# bq3DP_LCD.net
KiCad netlist of a schematic drawn in Altium Designer
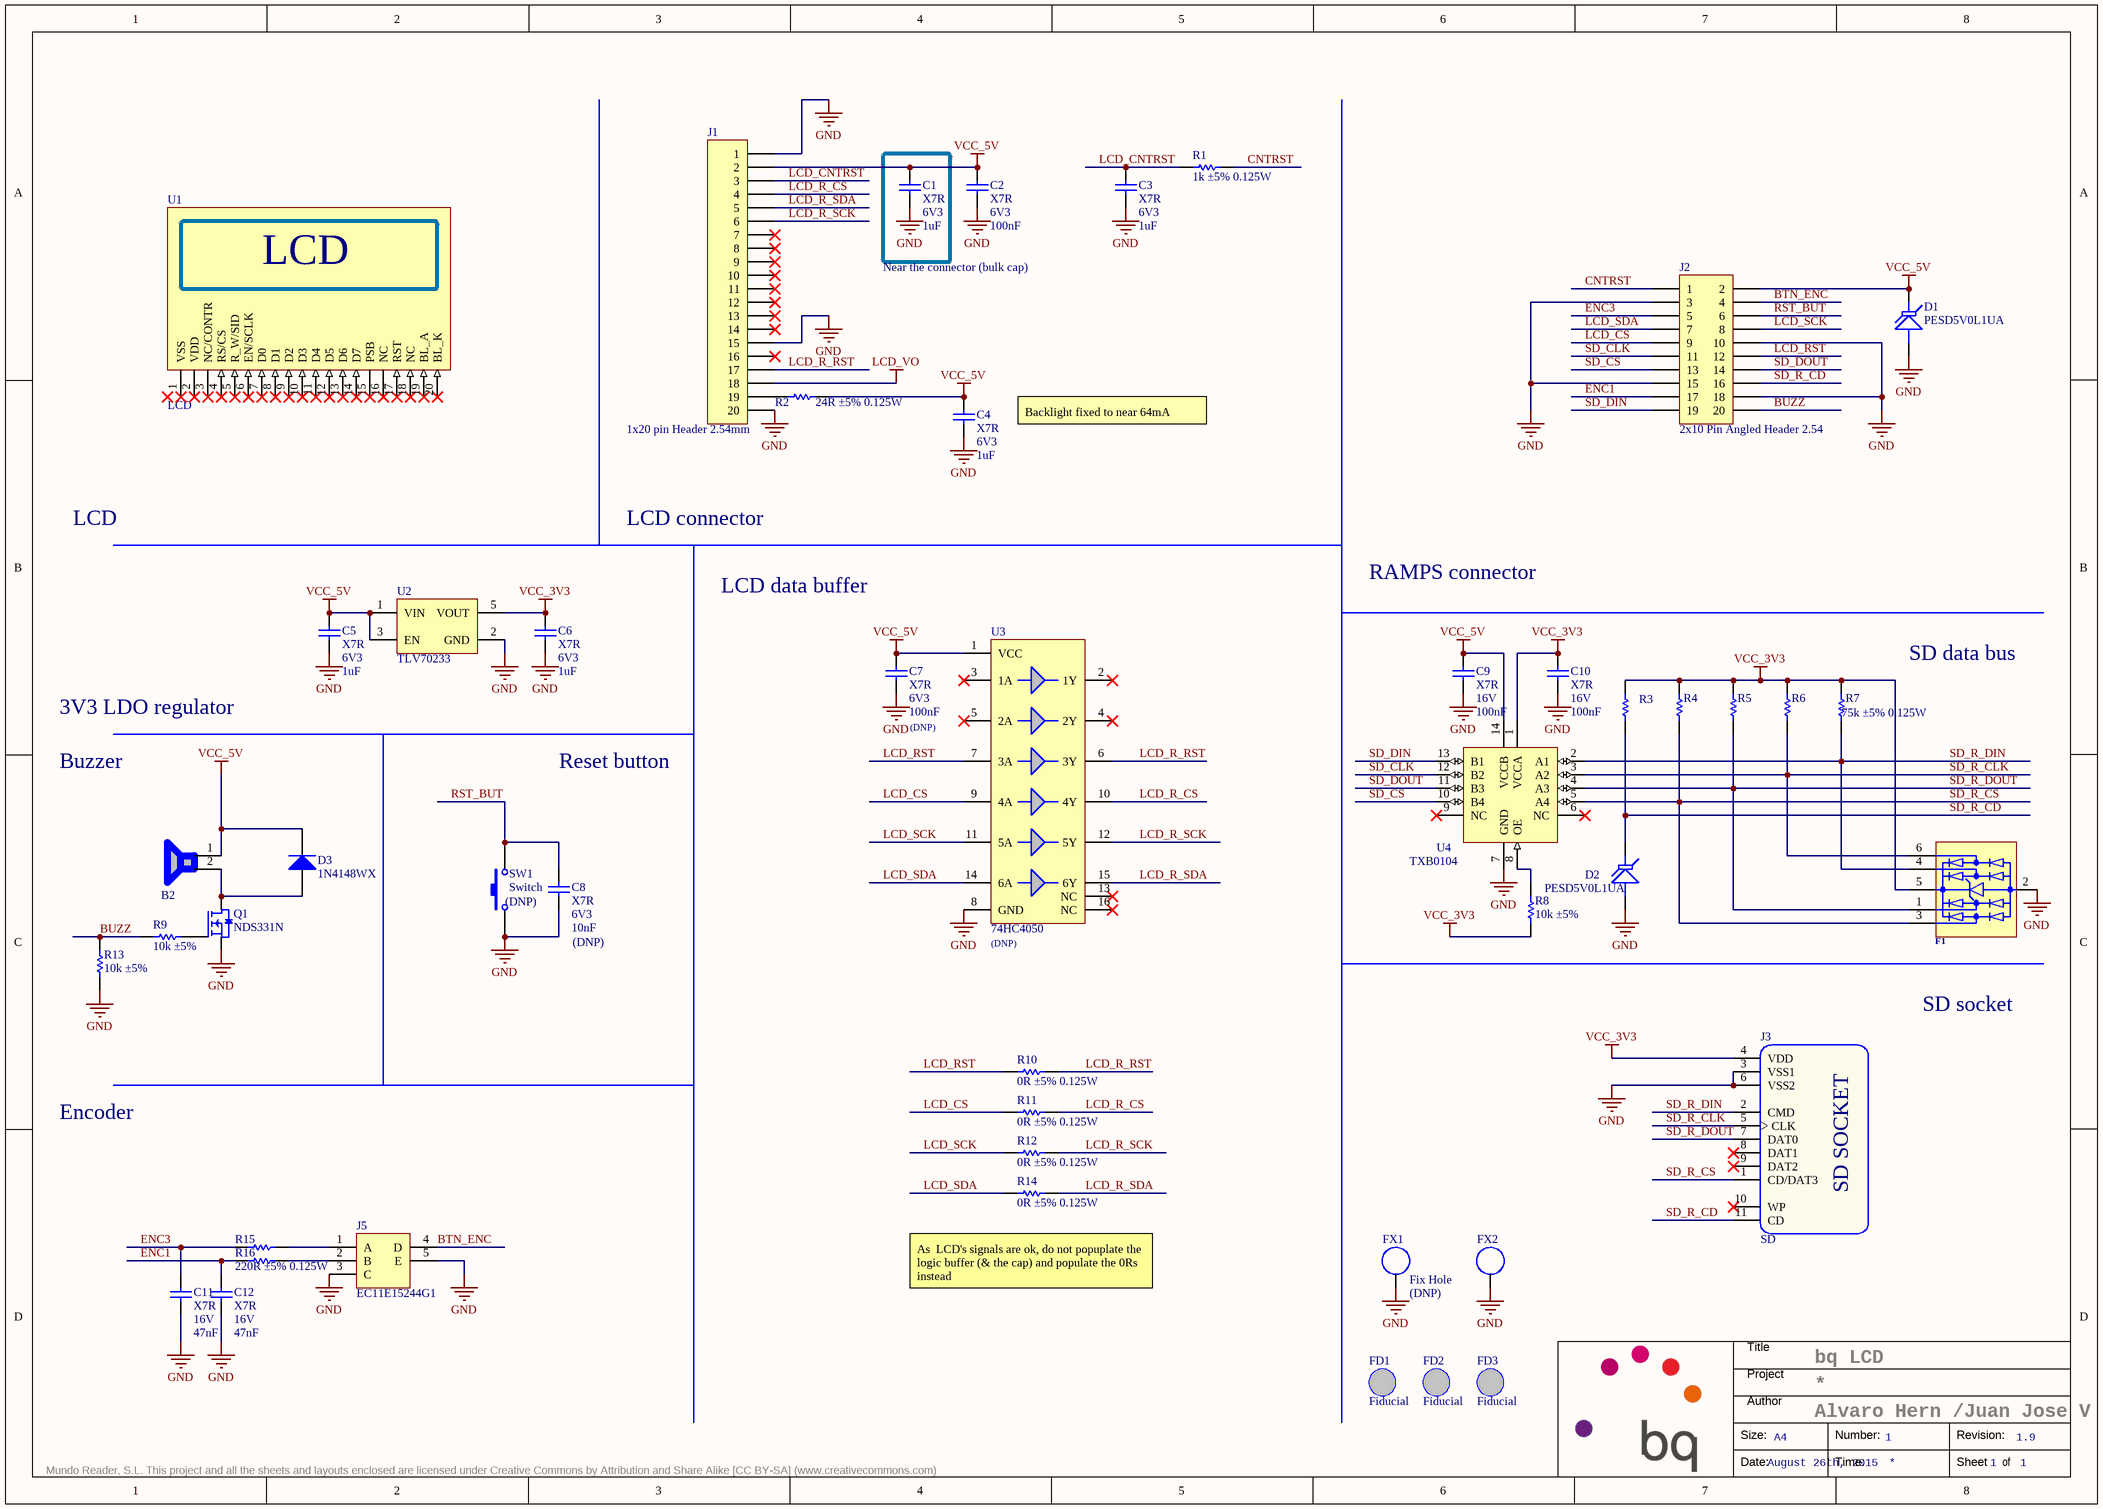
[diagram p0: bq3DP_LCD.SchDoc]

(export (version "E")
  (design (tool "Eeschema 10.0.6"))
  (components
    (comp (ref "B2")
      (value "BUZZER")
      (footprint "KXG1205C")
      (description "Buzzer")
      (fields (field (name "MANUFACTURER") "Kingstate Elect.") (field (name "PART NUMBER") "KXG1205C"))
      (libsource (lib "Electromechanical") (part "BUZZER"))
    )
    (comp (ref "C1")
      (value "Capacitor")
      (footprint "C0805")
      (fields
        (field (name "DIELECTRIC") "X7R")
        (field (name "VOLTAGE") "6V3")
        (field (name "CAPACITANCE") "1uF")
        (field (name "PART NUMBER") "C0805_1uF_6V3_±10%")
        (field (name "TOLERANCE") "±10%")
        (field (name "MANUFACTURER") "Kemet")
      )
      (libsource (lib "Pasives_Capacitor_SMD") (part "Capacitor"))
    )
    (comp (ref "C2")
      (value "Capacitor")
      (footprint "C0805")
      (fields
        (field (name "DIELECTRIC") "X7R")
        (field (name "VOLTAGE") "6V3")
        (field (name "CAPACITANCE") "100nF")
        (field (name "PART NUMBER") "C0805_100nF_6V3_±10%")
        (field (name "TOLERANCE") "±10%")
        (field (name "MANUFACTURER") "Kemet")
      )
      (libsource (lib "Pasives_Capacitor_SMD") (part "Capacitor"))
    )
    (comp (ref "C3")
      (value "Capacitor")
      (footprint "C0805")
      (fields
        (field (name "DIELECTRIC") "X7R")
        (field (name "VOLTAGE") "6V3")
        (field (name "CAPACITANCE") "1uF")
        (field (name "PART NUMBER") "C0805_1uF_6V3_±10%")
        (field (name "TOLERANCE") "±10%")
        (field (name "MANUFACTURER") "Kemet")
      )
      (libsource (lib "Pasives_Capacitor_SMD") (part "Capacitor"))
    )
    (comp (ref "C4")
      (value "Capacitor")
      (footprint "C0805")
      (fields
        (field (name "DIELECTRIC") "X7R")
        (field (name "VOLTAGE") "6V3")
        (field (name "CAPACITANCE") "1uF")
        (field (name "PART NUMBER") "C0805_1uF_6V3_±10%")
        (field (name "TOLERANCE") "±10%")
        (field (name "MANUFACTURER") "Kemet")
      )
      (libsource (lib "Pasives_Capacitor_SMD") (part "Capacitor"))
    )
    (comp (ref "C5")
      (value "Capacitor")
      (footprint "C0805")
      (fields
        (field (name "DIELECTRIC") "X7R")
        (field (name "VOLTAGE") "6V3")
        (field (name "CAPACITANCE") "1uF")
        (field (name "PART NUMBER") "C0805_1uF_6V3_±10%")
        (field (name "TOLERANCE") "±10%")
        (field (name "MANUFACTURER") "Kemet")
      )
      (libsource (lib "Pasives_Capacitor_SMD") (part "Capacitor"))
    )
    (comp (ref "C6")
      (value "Capacitor")
      (footprint "C0805")
      (fields
        (field (name "DIELECTRIC") "X7R")
        (field (name "VOLTAGE") "6V3")
        (field (name "CAPACITANCE") "1uF")
        (field (name "PART NUMBER") "C0805_1uF_6V3_±10%")
        (field (name "TOLERANCE") "±10%")
        (field (name "MANUFACTURER") "Kemet")
      )
      (libsource (lib "Pasives_Capacitor_SMD") (part "Capacitor"))
    )
    (comp (ref "C7")
      (value "Capacitor")
      (footprint "C0805")
      (fields
        (field (name "DIELECTRIC") "X7R")
        (field (name "VOLTAGE") "6V3")
        (field (name "CAPACITANCE") "100nF")
        (field (name "PART NUMBER") "C0805_100nF_6V3_±10%")
        (field (name "TOLERANCE") "±10%")
        (field (name "MANUFACTURER") "Kemet")
        (field (name "VARIANT") "(DNP)")
      )
      (libsource (lib "Pasives_Capacitor_SMD") (part "Capacitor"))
    )
    (comp (ref "C8")
      (value "Capacitor")
      (footprint "C0805")
      (fields
        (field (name "DIELECTRIC") "X7R")
        (field (name "VOLTAGE") "6V3")
        (field (name "CAPACITANCE") "10nF")
        (field (name "PART NUMBER") "C0805_10nF_6V3_±10%")
        (field (name "TOLERANCE") "±10%")
        (field (name "MANUFACTURER") "Kemet")
        (field (name "VARIANT") "(DNP)")
      )
      (libsource (lib "Pasives_Capacitor_SMD") (part "Capacitor"))
    )
    (comp (ref "C9")
      (value "Capacitor")
      (footprint "C0805")
      (description "Capacitor SMD")
      (fields
        (field (name "DIELECTRIC") "X7R")
        (field (name "VOLTAGE") "16V")
        (field (name "CAPACITANCE") "100nF")
        (field (name "PART NUMBER") "C0805_100nF_16V_±10%")
        (field (name "TOLERANCE") "±10%")
      )
      (libsource (lib "Pasives_Capacitor_SMD") (part "Capacitor"))
    )
    (comp (ref "C10")
      (value "Capacitor")
      (footprint "C0805")
      (description "Capacitor SMD")
      (fields
        (field (name "DIELECTRIC") "X7R")
        (field (name "VOLTAGE") "16V")
        (field (name "CAPACITANCE") "100nF")
        (field (name "PART NUMBER") "C0805_100nF_16V_±10%")
        (field (name "TOLERANCE") "±10%")
      )
      (libsource (lib "Pasives_Capacitor_SMD") (part "Capacitor"))
    )
    (comp (ref "C11")
      (value "Capacitor")
      (footprint "C0805")
      (description "Capacitor SMD")
      (fields
        (field (name "DIELECTRIC") "X7R")
        (field (name "VOLTAGE") "16V")
        (field (name "CAPACITANCE") "47nF")
        (field (name "PART NUMBER") "C0805_47nF_16V_±10%")
        (field (name "TOLERANCE") "±10%")
      )
      (libsource (lib "Pasives_Capacitor_SMD") (part "Capacitor"))
    )
    (comp (ref "C12")
      (value "Capacitor")
      (footprint "C0805")
      (description "Capacitor SMD")
      (fields
        (field (name "DIELECTRIC") "X7R")
        (field (name "VOLTAGE") "16V")
        (field (name "CAPACITANCE") "47nF")
        (field (name "PART NUMBER") "C0805_47nF_16V_±10%")
        (field (name "TOLERANCE") "±10%")
      )
      (libsource (lib "Pasives_Capacitor_SMD") (part "Capacitor"))
    )
    (comp (ref "D1")
      (value "PESD5V0L1UA")
      (footprint "SOD323")
      (description "Transient Suppression Diodes")
      (fields (field (name "VOLTAGE") "5Vdc") (field (name "MANUFACTURER") "NXP"))
      (libsource (lib "Protection") (part "Zener_TVS"))
    )
    (comp (ref "D2")
      (value "PESD5V0L1UA")
      (footprint "SOD323")
      (description "Transient Suppression Diodes")
      (fields (field (name "VOLTAGE") "5Vdc") (field (name "MANUFACTURER") "NXP"))
      (libsource (lib "Protection") (part "Zener_TVS"))
    )
    (comp (ref "D3")
      (value "1N4148WX")
      (footprint "SOD323")
      (description "Diodo")
      (fields (field (name "MANUFACTURER") "Micro Commercial Components"))
      (libsource (lib "Semiconductors_Diodes") (part "Diodo"))
    )
    (comp (ref "F1")
      (value "IP4220CZ6")
      (footprint "SOT23-6")
      (description "USB Dual ESD Protection")
      (fields (field (name "PART NUMBER") "USB ESD") (field (name "MANUFACTURER") "NXP"))
      (libsource (lib "Protection") (part "IP4220CZ6"))
    )
    (comp (ref "FD1")
      (value "Fiducial")
      (footprint "Fiducial")
      (libsource (lib "Miscelanea") (part "Fiducial"))
    )
    (comp (ref "FD2")
      (value "Fiducial")
      (footprint "Fiducial")
      (libsource (lib "Miscelanea") (part "Fiducial"))
    )
    (comp (ref "FD3")
      (value "Fiducial")
      (footprint "Fiducial")
      (libsource (lib "Miscelanea") (part "Fiducial"))
    )
    (comp (ref "FX1")
      (value "Fix Hole")
      (footprint "74760045")
      (fields
        (field (name "PART NUMBER") "Earth connection")
        (field (name "MANUFACTURER") "Wurth")
        (field (name "VARIANT") "(DNP)")
      )
      (libsource (lib "Miscelanea") (part "Fix Hole"))
    )
    (comp (ref "FX2")
      (value "Fix Hole")
      (footprint "7466214")
      (fields (field (name "PART NUMBER") "Earth SMD connection") (field (name "MANUFACTURER") "Wurth"))
      (libsource (lib "Miscelanea") (part "Fix Hole"))
    )
    (comp (ref "J1")
      (value "1x20 pin Header 2.54mm")
      (footprint "1x20 Pin Header 2.54")
      (fields (field (name "PART NUMBER") "CON_PH_THT2.54_20") (field (name "MANUFACTURER") "Samtec"))
      (libsource (lib "Conectores_PinHeader_2.54") (part "1x20 pin Header 2.54mm"))
    )
    (comp (ref "J2")
      (value "2x10 Pin Angled Header 2.54")
      (footprint "2x10 Pin Angled Header 2.54")
      (description "20 pin Dual Angled Header 2.54mm")
      (fields (field (name "PART NUMBER") "CON_DPH_THTA2.54_20") (field (name "MANUFACTURER") "Samtec"))
      (libsource (lib "Conectores_PinHeader_2.54") (part "2x10 Pin Angled Header 2.54"))
    )
    (comp (ref "J3")
      (value "SD")
      (footprint "SD")
      (fields (field (name "MANUFACTURER") "Wurth"))
      (libsource (lib "Connectors_Storage") (part "SD"))
    )
    (comp (ref "J5")
      (value "Encoder_ALPS")
      (footprint "Encoder_EC11")
      (description "Encoder 2-ph w/button ALPS")
      (fields
        (field (name "ORDERINGCODE") "EC11E15244G1")
        (field (name "MANUFACTURER") "ALPS")
        (field (name "PART NUMBER") "Encoder_EC11")
      )
      (libsource (lib "Electromechanical") (part "Encoder_ALPS"))
    )
    (comp (ref "Q1")
      (value "NDS331N")
      (footprint "SOT23-3")
      (description "Mosfet Channel N Enhancement Mode")
      (fields (field (name "MANUFACTURER") "Fairchild Semiconductor"))
      (libsource (lib "Semiconductors_Transistors") (part "Mosfet_N"))
    )
    (comp (ref "R1")
      (value "1k ±5% 0.125W")
      (footprint "R0805")
      (description "Resistor")
      (fields (field (name "TOLERANCE") "±5%") (field (name "POWER") "0.125W"))
      (libsource (lib "Pasives_Resistor_SMD") (part "Resistor"))
    )
    (comp (ref "R2")
      (value "24R ±5% 0.125W")
      (footprint "R0805")
      (description "Resistor")
      (fields (field (name "TOLERANCE") "±5%") (field (name "POWER") "0.125W"))
      (libsource (lib "Pasives_Resistor_SMD") (part "Resistor"))
    )
    (comp (ref "R3")
      (value "Resistor")
      (footprint "R0805")
      (description "Resistor, SMD")
      (fields (field (name "TOLERANCE") "±5%") (field (name "POWER") "0.125W"))
      (libsource (lib "Pasives_Resistor_SMD") (part "Resistor"))
    )
    (comp (ref "R4")
      (value "Resistor")
      (footprint "R0805")
      (description "Resistor, SMD")
      (fields (field (name "TOLERANCE") "±5%") (field (name "POWER") "0.125W"))
      (libsource (lib "Pasives_Resistor_SMD") (part "Resistor"))
    )
    (comp (ref "R5")
      (value "Resistor")
      (footprint "R0805")
      (description "Resistor, SMD")
      (fields (field (name "TOLERANCE") "±5%") (field (name "POWER") "0.125W"))
      (libsource (lib "Pasives_Resistor_SMD") (part "Resistor"))
    )
    (comp (ref "R6")
      (value "Resistor")
      (footprint "R0805")
      (description "Resistor, SMD")
      (fields (field (name "TOLERANCE") "±5%") (field (name "POWER") "0.125W"))
      (libsource (lib "Pasives_Resistor_SMD") (part "Resistor"))
    )
    (comp (ref "R7")
      (value "75k ±5% 0.125W")
      (footprint "R0805")
      (description "Resistor, SMD")
      (fields (field (name "TOLERANCE") "±5%") (field (name "POWER") "0.125W"))
      (libsource (lib "Pasives_Resistor_SMD") (part "Resistor"))
    )
    (comp (ref "R8")
      (value "10k ±5%")
      (footprint "R0805")
      (description "Resistor")
      (fields (field (name "TOLERANCE") "±5%") (field (name "POWER") "0.125W"))
      (libsource (lib "Pasives_Resistor_SMD") (part "Resistor"))
    )
    (comp (ref "R9")
      (value "10k ±5%")
      (footprint "R0805")
      (description "Resistor")
      (fields (field (name "TOLERANCE") "±5%") (field (name "POWER") "0.125W"))
      (libsource (lib "Pasives_Resistor_SMD") (part "Resistor"))
    )
    (comp (ref "R10")
      (value "0R ±5% 0.125W")
      (footprint "R0805")
      (description "Resistor, SMD")
      (fields (field (name "TOLERANCE") "±5%") (field (name "POWER") "0.125W"))
      (libsource (lib "Pasives_Resistor_SMD") (part "Resistor"))
    )
    (comp (ref "R11")
      (value "0R ±5% 0.125W")
      (footprint "R0805")
      (description "Resistor, SMD")
      (fields (field (name "TOLERANCE") "±5%") (field (name "POWER") "0.125W"))
      (libsource (lib "Pasives_Resistor_SMD") (part "Resistor"))
    )
    (comp (ref "R12")
      (value "0R ±5% 0.125W")
      (footprint "R0805")
      (description "Resistor, SMD")
      (fields (field (name "TOLERANCE") "±5%") (field (name "POWER") "0.125W"))
      (libsource (lib "Pasives_Resistor_SMD") (part "Resistor"))
    )
    (comp (ref "R13")
      (value "10k ±5%")
      (footprint "R0805")
      (description "Resistor")
      (fields (field (name "TOLERANCE") "±5%") (field (name "POWER") "0.125W"))
      (libsource (lib "Pasives_Resistor_SMD") (part "Resistor"))
    )
    (comp (ref "R14")
      (value "0R ±5% 0.125W")
      (footprint "R0805")
      (description "Resistor, SMD")
      (fields (field (name "TOLERANCE") "±5%") (field (name "POWER") "0.125W"))
      (libsource (lib "Pasives_Resistor_SMD") (part "Resistor"))
    )
    (comp (ref "R15")
      (value "Resistor")
      (footprint "R0805")
      (description "Resistor, SMD")
      (fields (field (name "TOLERANCE") "±5%") (field (name "POWER") "0.125W"))
      (libsource (lib "Pasives_Resistor_SMD") (part "Resistor"))
    )
    (comp (ref "R16")
      (value "220R ±5% 0.125W")
      (footprint "R0805")
      (description "Resistor, SMD")
      (fields (field (name "TOLERANCE") "±5%") (field (name "POWER") "0.125W"))
      (libsource (lib "Pasives_Resistor_SMD") (part "Resistor"))
    )
    (comp (ref "SW1")
      (value "Switch")
      (footprint "SW_SMD_6.0x3.8")
      (description "Micro miniature pushbutton surface Switch")
      (fields
        (field (name "PART NUMBER") "SW SMD")
        (field (name "MANUFACTURER") "Würth Elektronik")
        (field (name "VARIANT") "(DNP)")
      )
      (libsource (lib "Electromechanical") (part "Switch"))
    )
    (comp (ref "U1")
      (value "LCD")
      (footprint "LCD_Graphic_128x64")
      (description "LCD 128x64 dot 93x70mm")
      (fields (field (name "PART NUMBER") "LCD_graph") (field (name "MANUFACTURER") "Winstar"))
      (libsource (lib "Optoelectronics") (part "LCD"))
    )
    (comp (ref "U2")
      (value "TLV70233")
      (footprint "SOT23-5")
      (description "300mA LowIQ Low-dropout Regulator")
      (fields (field (name "MANUFACTURER") "Texas Instruments"))
      (libsource (lib "Power_Regulator") (part "TLV702XX"))
    )
    (comp (ref "U3")
      (value "74HC4050")
      (footprint "SO16")
      (description "Hex non-inverting HIGH-to-LOW level shifter")
      (fields
        (field (name "PART NUMBER") "HEF4050B")
        (field (name "MANUFACTURER") "NXP")
        (field (name "VARIANT") "(DNP)")
      )
      (libsource (lib "Transceiver") (part "74HC4050"))
    )
    (comp (ref "U4")
      (value "TXB0104")
      (footprint "QFN14")
      (description "Voltage Translator, Quad")
      (fields (field (name "MANUFACTURER") "Texas Instruments"))
      (libsource (lib "Voltage_translator") (part "TXB0104"))
    )
  )
  (nets
    (net (code "1") (name "/BTN_ENC") (class "Default")
      (node (ref "J2") (pin "4") (pinfunction "4_4") (pintype "passive"))
      (node (ref "J5") (pin "4") (pinfunction "D_4") (pintype "power_in"))
    )
    (net (code "2") (name "/BUZZ") (class "Default")
      (node (ref "J2") (pin "20") (pinfunction "20_20") (pintype "passive"))
      (node (ref "R13") (pin "2") (pinfunction "2_2") (pintype "passive"))
      (node (ref "R9") (pin "2") (pinfunction "2_2") (pintype "passive"))
    )
    (net (code "3") (name "/CNTRST") (class "Default")
      (node (ref "J2") (pin "1") (pinfunction "1_1") (pintype "passive"))
      (node (ref "R1") (pin "2") (pinfunction "2_2") (pintype "passive"))
    )
    (net (code "4") (name "/ENC1") (class "Default")
      (node (ref "C12") (pin "2") (pinfunction "2_2") (pintype "passive"))
      (node (ref "J2") (pin "17") (pinfunction "17_17") (pintype "passive"))
      (node (ref "R16") (pin "1") (pinfunction "1_1") (pintype "passive"))
    )
    (net (code "5") (name "/ENC3") (class "Default")
      (node (ref "C11") (pin "2") (pinfunction "2_2") (pintype "passive"))
      (node (ref "J2") (pin "5") (pinfunction "5_5") (pintype "passive"))
      (node (ref "R15") (pin "1") (pinfunction "1_1") (pintype "passive"))
    )
    (net (code "6") (name "/LCD_CNTRST") (class "Default")
      (node (ref "C3") (pin "2") (pinfunction "2_2") (pintype "passive"))
      (node (ref "J1") (pin "3") (pinfunction "3_3") (pintype "passive"))
      (node (ref "R1") (pin "1") (pinfunction "1_1") (pintype "passive"))
    )
    (net (code "7") (name "/LCD_CS") (class "Default")
      (node (ref "J2") (pin "9") (pinfunction "9_9") (pintype "passive"))
      (node (ref "R11") (pin "1") (pinfunction "1_1") (pintype "passive"))
      (node (ref "U3") (pin "9") (pinfunction "4A_9") (pintype "power_in"))
    )
    (net (code "8") (name "/LCD_RST") (class "Default")
      (node (ref "J2") (pin "12") (pinfunction "12_12") (pintype "passive"))
      (node (ref "R10") (pin "1") (pinfunction "1_1") (pintype "passive"))
      (node (ref "U3") (pin "7") (pinfunction "3A_7") (pintype "power_in"))
    )
    (net (code "9") (name "/LCD_R_CS") (class "Default")
      (node (ref "J1") (pin "4") (pinfunction "4_4") (pintype "passive"))
      (node (ref "R11") (pin "2") (pinfunction "2_2") (pintype "passive"))
      (node (ref "U3") (pin "10") (pinfunction "4Y_10") (pintype "power_in"))
    )
    (net (code "10") (name "/LCD_R_RST") (class "Default")
      (node (ref "J1") (pin "17") (pinfunction "17_17") (pintype "passive"))
      (node (ref "R10") (pin "2") (pinfunction "2_2") (pintype "passive"))
      (node (ref "U3") (pin "6") (pinfunction "3Y_6") (pintype "power_in"))
    )
    (net (code "11") (name "/LCD_R_SCK") (class "Default")
      (node (ref "J1") (pin "6") (pinfunction "6_6") (pintype "passive"))
      (node (ref "R12") (pin "2") (pinfunction "2_2") (pintype "passive"))
      (node (ref "U3") (pin "12") (pinfunction "5Y_12") (pintype "power_in"))
    )
    (net (code "12") (name "/LCD_R_SDA") (class "Default")
      (node (ref "J1") (pin "5") (pinfunction "5_5") (pintype "passive"))
      (node (ref "R14") (pin "2") (pinfunction "2_2") (pintype "passive"))
      (node (ref "U3") (pin "15") (pinfunction "6Y_15") (pintype "power_in"))
    )
    (net (code "13") (name "/LCD_SCK") (class "Default")
      (node (ref "J2") (pin "8") (pinfunction "8_8") (pintype "passive"))
      (node (ref "R12") (pin "1") (pinfunction "1_1") (pintype "passive"))
      (node (ref "U3") (pin "11") (pinfunction "5A_11") (pintype "power_in"))
    )
    (net (code "14") (name "/LCD_SDA") (class "Default")
      (node (ref "J2") (pin "7") (pinfunction "7_7") (pintype "passive"))
      (node (ref "R14") (pin "1") (pinfunction "1_1") (pintype "passive"))
      (node (ref "U3") (pin "14") (pinfunction "6A_14") (pintype "power_in"))
    )
    (net (code "15") (name "/RST_BUT") (class "Default")
      (node (ref "C8") (pin "2") (pinfunction "2_2") (pintype "passive"))
      (node (ref "J2") (pin "6") (pinfunction "6_6") (pintype "passive"))
      (node (ref "SW1") (pin "2") (pinfunction "2_2") (pintype "passive"))
    )
    (net (code "16") (name "/SD_CLK") (class "Default")
      (node (ref "J2") (pin "11") (pinfunction "11_11") (pintype "passive"))
      (node (ref "U4") (pin "12") (pinfunction "B2_12") (pintype "bidirectional"))
    )
    (net (code "17") (name "/SD_CS") (class "Default")
      (node (ref "J2") (pin "13") (pinfunction "13_13") (pintype "passive"))
      (node (ref "U4") (pin "10") (pinfunction "B4_10") (pintype "bidirectional"))
    )
    (net (code "18") (name "/SD_DIN") (class "Default")
      (node (ref "J2") (pin "19") (pinfunction "19_19") (pintype "passive"))
      (node (ref "U4") (pin "13") (pinfunction "B1_13") (pintype "bidirectional"))
    )
    (net (code "19") (name "/SD_DOUT") (class "Default")
      (node (ref "J2") (pin "14") (pinfunction "14_14") (pintype "passive"))
      (node (ref "U4") (pin "11") (pinfunction "B3_11") (pintype "bidirectional"))
    )
    (net (code "20") (name "/SD_R_CD") (class "Default")
      (node (ref "D2") (pin "K") (pinfunction "K_K") (pintype "passive"))
      (node (ref "J2") (pin "16") (pinfunction "16_16") (pintype "passive"))
      (node (ref "J3") (pin "11") (pinfunction "CD_11") (pintype "passive"))
      (node (ref "R3") (pin "1") (pinfunction "1_1") (pintype "passive"))
    )
    (net (code "21") (name "/SD_R_CLK") (class "Default")
      (node (ref "F1") (pin "6") (pinfunction "6_6") (pintype "passive"))
      (node (ref "J3") (pin "5") (pinfunction "CLK_5") (pintype "passive"))
      (node (ref "R6") (pin "1") (pinfunction "1_1") (pintype "passive"))
      (node (ref "U4") (pin "3") (pinfunction "A2_3") (pintype "bidirectional"))
    )
    (net (code "22") (name "/SD_R_CS") (class "Default")
      (node (ref "F1") (pin "3") (pinfunction "3_3") (pintype "passive"))
      (node (ref "J3") (pin "1") (pinfunction "CD/DAT3_1") (pintype "passive"))
      (node (ref "R4") (pin "1") (pinfunction "1_1") (pintype "passive"))
      (node (ref "U4") (pin "5") (pinfunction "A4_5") (pintype "bidirectional"))
    )
    (net (code "23") (name "/SD_R_DIN") (class "Default")
      (node (ref "F1") (pin "4") (pinfunction "4_4") (pintype "passive"))
      (node (ref "J3") (pin "2") (pinfunction "CMD_2") (pintype "passive"))
      (node (ref "R7") (pin "1") (pinfunction "1_1") (pintype "passive"))
      (node (ref "U4") (pin "2") (pinfunction "A1_2") (pintype "bidirectional"))
    )
    (net (code "24") (name "/SD_R_DOUT") (class "Default")
      (node (ref "F1") (pin "1") (pinfunction "1_1") (pintype "passive"))
      (node (ref "J3") (pin "7") (pinfunction "DAT0_7") (pintype "passive"))
      (node (ref "R5") (pin "1") (pinfunction "1_1") (pintype "passive"))
      (node (ref "U4") (pin "4") (pinfunction "A3_4") (pintype "bidirectional"))
    )
    (net (code "25") (name "GND") (class "Default")
      (node (ref "C1") (pin "1") (pinfunction "1_1") (pintype "passive"))
      (node (ref "C10") (pin "1") (pinfunction "1_1") (pintype "passive"))
      (node (ref "C11") (pin "1") (pinfunction "1_1") (pintype "passive"))
      (node (ref "C12") (pin "1") (pinfunction "1_1") (pintype "passive"))
      (node (ref "C2") (pin "1") (pinfunction "1_1") (pintype "passive"))
      (node (ref "C3") (pin "1") (pinfunction "1_1") (pintype "passive"))
      (node (ref "C4") (pin "1") (pinfunction "1_1") (pintype "passive"))
      (node (ref "C5") (pin "1") (pinfunction "1_1") (pintype "passive"))
      (node (ref "C6") (pin "1") (pinfunction "1_1") (pintype "passive"))
      (node (ref "C7") (pin "1") (pinfunction "1_1") (pintype "passive"))
      (node (ref "C8") (pin "1") (pinfunction "1_1") (pintype "passive"))
      (node (ref "C9") (pin "1") (pinfunction "1_1") (pintype "passive"))
      (node (ref "D1") (pin "A") (pinfunction "A_A") (pintype "passive"))
      (node (ref "D2") (pin "A") (pinfunction "A_A") (pintype "passive"))
      (node (ref "F1") (pin "2") (pinfunction "2_2") (pintype "passive"))
      (node (ref "FX1") (pin "1") (pinfunction "1_1") (pintype "passive"))
      (node (ref "FX2") (pin "1") (pinfunction "1_1") (pintype "passive"))
      (node (ref "J1") (pin "1") (pinfunction "1_1") (pintype "passive"))
      (node (ref "J1") (pin "15") (pinfunction "15_15") (pintype "passive"))
      (node (ref "J1") (pin "20") (pinfunction "20_20") (pintype "tri_state"))
      (node (ref "J2") (pin "10") (pinfunction "10_10") (pintype "passive"))
      (node (ref "J2") (pin "15") (pinfunction "15_15") (pintype "passive"))
      (node (ref "J2") (pin "18") (pinfunction "18_18") (pintype "passive"))
      (node (ref "J2") (pin "3") (pinfunction "3_3") (pintype "passive"))
      (node (ref "J3") (pin "3") (pinfunction "VSS1_3") (pintype "passive"))
      (node (ref "J3") (pin "6") (pinfunction "VSS2_6") (pintype "passive"))
      (node (ref "J5") (pin "3") (pinfunction "C_3") (pintype "power_in"))
      (node (ref "J5") (pin "5") (pinfunction "E_5") (pintype "power_in"))
      (node (ref "Q1") (pin "2") (pinfunction "S_2") (pintype "passive"))
      (node (ref "R13") (pin "1") (pinfunction "1_1") (pintype "passive"))
      (node (ref "SW1") (pin "1") (pinfunction "1_1") (pintype "passive"))
      (node (ref "U2") (pin "2") (pinfunction "GND_2") (pintype "power_in"))
      (node (ref "U3") (pin "8") (pinfunction "GND_8") (pintype "power_in"))
      (node (ref "U4") (pin "7") (pinfunction "GND_7") (pintype "power_in"))
    )
    (net (code "26") (name "LCD_VO") (class "Default")
      (node (ref "J1") (pin "18") (pinfunction "18_18") (pintype "passive"))
    )
    (net (code "27") (name "Net-(J1-Pad19)") (class "Default")
      (node (ref "J1") (pin "19") (pinfunction "19_19") (pintype "tri_state"))
      (node (ref "R2") (pin "1") (pinfunction "1_1") (pintype "passive"))
    )
    (net (code "28") (name "Net-(J5-A)") (class "Default")
      (node (ref "J5") (pin "1") (pinfunction "A_1") (pintype "power_in"))
      (node (ref "R15") (pin "2") (pinfunction "2_2") (pintype "passive"))
    )
    (net (code "29") (name "Net-(J5-B)") (class "Default")
      (node (ref "J5") (pin "2") (pinfunction "B_2") (pintype "power_in"))
      (node (ref "R16") (pin "2") (pinfunction "2_2") (pintype "passive"))
    )
    (net (code "30") (name "Net-(Q1-D)") (class "Default")
      (node (ref "B2") (pin "2") (pinfunction "2_2") (pintype "passive"))
      (node (ref "D3") (pin "A") (pinfunction "A_A") (pintype "passive"))
      (node (ref "Q1") (pin "3") (pinfunction "D_3") (pintype "passive"))
    )
    (net (code "31") (name "Net-(Q1-G)") (class "Default")
      (node (ref "Q1") (pin "1") (pinfunction "G_1") (pintype "passive"))
      (node (ref "R9") (pin "1") (pinfunction "1_1") (pintype "passive"))
    )
    (net (code "32") (name "Net-(U4-OE)") (class "Default")
      (node (ref "R8") (pin "1") (pinfunction "1_1") (pintype "passive"))
      (node (ref "U4") (pin "8") (pinfunction "OE_8") (pintype "input"))
    )
    (net (code "33") (name "VCC_3V3") (class "Default")
      (node (ref "C10") (pin "2") (pinfunction "2_2") (pintype "passive"))
      (node (ref "C6") (pin "2") (pinfunction "2_2") (pintype "passive"))
      (node (ref "F1") (pin "5") (pinfunction "5_5") (pintype "passive"))
      (node (ref "J3") (pin "4") (pinfunction "VDD_4") (pintype "passive"))
      (node (ref "R3") (pin "2") (pinfunction "2_2") (pintype "passive"))
      (node (ref "R4") (pin "2") (pinfunction "2_2") (pintype "passive"))
      (node (ref "R5") (pin "2") (pinfunction "2_2") (pintype "passive"))
      (node (ref "R6") (pin "2") (pinfunction "2_2") (pintype "passive"))
      (node (ref "R7") (pin "2") (pinfunction "2_2") (pintype "passive"))
      (node (ref "R8") (pin "2") (pinfunction "2_2") (pintype "passive"))
      (node (ref "U2") (pin "5") (pinfunction "VOUT_5") (pintype "power_in"))
      (node (ref "U4") (pin "1") (pinfunction "VCCA_1") (pintype "power_in"))
    )
    (net (code "34") (name "VCC_5V") (class "Default")
      (node (ref "B2") (pin "1") (pinfunction "1_1") (pintype "passive"))
      (node (ref "C1") (pin "2") (pinfunction "2_2") (pintype "passive"))
      (node (ref "C2") (pin "2") (pinfunction "2_2") (pintype "passive"))
      (node (ref "C4") (pin "2") (pinfunction "2_2") (pintype "passive"))
      (node (ref "C5") (pin "2") (pinfunction "2_2") (pintype "passive"))
      (node (ref "C7") (pin "2") (pinfunction "2_2") (pintype "passive"))
      (node (ref "C9") (pin "2") (pinfunction "2_2") (pintype "passive"))
      (node (ref "D1") (pin "K") (pinfunction "K_K") (pintype "passive"))
      (node (ref "D3") (pin "K") (pinfunction "K_K") (pintype "passive"))
      (node (ref "J1") (pin "2") (pinfunction "2_2") (pintype "passive"))
      (node (ref "J2") (pin "2") (pinfunction "2_2") (pintype "passive"))
      (node (ref "R2") (pin "2") (pinfunction "2_2") (pintype "passive"))
      (node (ref "U2") (pin "1") (pinfunction "VIN_1") (pintype "power_in"))
      (node (ref "U2") (pin "3") (pinfunction "EN_3") (pintype "power_in"))
      (node (ref "U3") (pin "1") (pinfunction "VCC_1") (pintype "power_in"))
      (node (ref "U4") (pin "14") (pinfunction "VCCB_14") (pintype "power_in"))
    )
    (net (code "35") (name "unconnected-(J1-Pad7)") (class "Default")
      (node (ref "J1") (pin "7") (pinfunction "7_7") (pintype "passive+no_connect"))
    )
    (net (code "36") (name "unconnected-(J1-Pad8)") (class "Default")
      (node (ref "J1") (pin "8") (pinfunction "8_8") (pintype "passive+no_connect"))
    )
    (net (code "37") (name "unconnected-(J1-Pad9)") (class "Default")
      (node (ref "J1") (pin "9") (pinfunction "9_9") (pintype "passive+no_connect"))
    )
    (net (code "38") (name "unconnected-(J1-Pad10)") (class "Default")
      (node (ref "J1") (pin "10") (pinfunction "10_10") (pintype "passive+no_connect"))
    )
    (net (code "39") (name "unconnected-(J1-Pad11)") (class "Default")
      (node (ref "J1") (pin "11") (pinfunction "11_11") (pintype "passive+no_connect"))
    )
    (net (code "40") (name "unconnected-(J1-Pad12)") (class "Default")
      (node (ref "J1") (pin "12") (pinfunction "12_12") (pintype "passive+no_connect"))
    )
    (net (code "41") (name "unconnected-(J1-Pad13)") (class "Default")
      (node (ref "J1") (pin "13") (pinfunction "13_13") (pintype "passive+no_connect"))
    )
    (net (code "42") (name "unconnected-(J1-Pad14)") (class "Default")
      (node (ref "J1") (pin "14") (pinfunction "14_14") (pintype "passive+no_connect"))
    )
    (net (code "43") (name "unconnected-(J1-Pad16)") (class "Default")
      (node (ref "J1") (pin "16") (pinfunction "16_16") (pintype "passive+no_connect"))
    )
    (net (code "44") (name "unconnected-(J3-DAT1-Pad8)") (class "Default")
      (node (ref "J3") (pin "8") (pinfunction "DAT1_8") (pintype "passive+no_connect"))
    )
    (net (code "45") (name "unconnected-(J3-DAT2-Pad9)") (class "Default")
      (node (ref "J3") (pin "9") (pinfunction "DAT2_9") (pintype "passive+no_connect"))
    )
    (net (code "46") (name "unconnected-(J3-WP-Pad10)") (class "Default")
      (node (ref "J3") (pin "10") (pinfunction "WP_10") (pintype "passive+no_connect"))
    )
    (net (code "47") (name "unconnected-(U1-BL_A-Pad19)") (class "Default")
      (node (ref "U1") (pin "19") (pinfunction "BL_A_19") (pintype "input+no_connect"))
    )
    (net (code "48") (name "unconnected-(U1-BL_K-Pad20)") (class "Default")
      (node (ref "U1") (pin "20") (pinfunction "BL_K_20") (pintype "input+no_connect"))
    )
    (net (code "49") (name "unconnected-(U1-D0-Pad7)") (class "Default")
      (node (ref "U1") (pin "7") (pinfunction "D0_7") (pintype "input+no_connect"))
    )
    (net (code "50") (name "unconnected-(U1-D1-Pad8)") (class "Default")
      (node (ref "U1") (pin "8") (pinfunction "D1_8") (pintype "input+no_connect"))
    )
    (net (code "51") (name "unconnected-(U1-D2-Pad9)") (class "Default")
      (node (ref "U1") (pin "9") (pinfunction "D2_9") (pintype "input+no_connect"))
    )
    (net (code "52") (name "unconnected-(U1-D3-Pad10)") (class "Default")
      (node (ref "U1") (pin "10") (pinfunction "D3_10") (pintype "input+no_connect"))
    )
    (net (code "53") (name "unconnected-(U1-D4-Pad11)") (class "Default")
      (node (ref "U1") (pin "11") (pinfunction "D4_11") (pintype "input+no_connect"))
    )
    (net (code "54") (name "unconnected-(U1-D5-Pad12)") (class "Default")
      (node (ref "U1") (pin "12") (pinfunction "D5_12") (pintype "input+no_connect"))
    )
    (net (code "55") (name "unconnected-(U1-D6-Pad13)") (class "Default")
      (node (ref "U1") (pin "13") (pinfunction "D6_13") (pintype "input+no_connect"))
    )
    (net (code "56") (name "unconnected-(U1-D7-Pad14)") (class "Default")
      (node (ref "U1") (pin "14") (pinfunction "D7_14") (pintype "input+no_connect"))
    )
    (net (code "57") (name "unconnected-(U1-EN{slash}SCLK-Pad6)") (class "Default")
      (node (ref "U1") (pin "6") (pinfunction "EN/SCLK_6") (pintype "input+no_connect"))
    )
    (net (code "58") (name "unconnected-(U1-NC-Pad16)") (class "Default")
      (node (ref "U1") (pin "16") (pinfunction "NC_16") (pintype "passive+no_connect"))
    )
    (net (code "59") (name "unconnected-(U1-NC-Pad18)") (class "Default")
      (node (ref "U1") (pin "18") (pinfunction "NC_18") (pintype "input+no_connect"))
    )
    (net (code "60") (name "unconnected-(U1-NC{slash}CONTR-Pad3)") (class "Default")
      (node (ref "U1") (pin "3") (pinfunction "NC/CONTR_3") (pintype "power_in+no_connect"))
    )
    (net (code "61") (name "unconnected-(U1-PSB-Pad15)") (class "Default")
      (node (ref "U1") (pin "15") (pinfunction "PSB_15") (pintype "passive+no_connect"))
    )
    (net (code "62") (name "unconnected-(U1-RST-Pad17)") (class "Default")
      (node (ref "U1") (pin "17") (pinfunction "RST_17") (pintype "input+no_connect"))
    )
    (net (code "63") (name "unconnected-(U1-RS{slash}CS-Pad4)") (class "Default")
      (node (ref "U1") (pin "4") (pinfunction "RS/CS_4") (pintype "input+no_connect"))
    )
    (net (code "64") (name "unconnected-(U1-R_W{slash}SID-Pad5)") (class "Default")
      (node (ref "U1") (pin "5") (pinfunction "R_W/SID_5") (pintype "input+no_connect"))
    )
    (net (code "65") (name "unconnected-(U1-VDD-Pad2)") (class "Default")
      (node (ref "U1") (pin "2") (pinfunction "VDD_2") (pintype "power_in+no_connect"))
    )
    (net (code "66") (name "unconnected-(U1-VSS-Pad1)") (class "Default")
      (node (ref "U1") (pin "1") (pinfunction "VSS_1") (pintype "power_in+no_connect"))
    )
    (net (code "67") (name "unconnected-(U3-1A-Pad3)") (class "Default")
      (node (ref "U3") (pin "3") (pinfunction "1A_3") (pintype "power_in+no_connect"))
    )
    (net (code "68") (name "unconnected-(U3-1Y-Pad2)") (class "Default")
      (node (ref "U3") (pin "2") (pinfunction "1Y_2") (pintype "power_in+no_connect"))
    )
    (net (code "69") (name "unconnected-(U3-2A-Pad5)") (class "Default")
      (node (ref "U3") (pin "5") (pinfunction "2A_5") (pintype "power_in+no_connect"))
    )
    (net (code "70") (name "unconnected-(U3-2Y-Pad4)") (class "Default")
      (node (ref "U3") (pin "4") (pinfunction "2Y_4") (pintype "power_in+no_connect"))
    )
    (net (code "71") (name "unconnected-(U3-NC-Pad13)") (class "Default")
      (node (ref "U3") (pin "13") (pinfunction "NC_13") (pintype "power_in+no_connect"))
    )
    (net (code "72") (name "unconnected-(U3-NC-Pad16)") (class "Default")
      (node (ref "U3") (pin "16") (pinfunction "NC_16") (pintype "power_in+no_connect"))
    )
    (net (code "73") (name "unconnected-(U4-NC-Pad6)") (class "Default")
      (node (ref "U4") (pin "6") (pinfunction "NC_6") (pintype "passive+no_connect"))
    )
    (net (code "74") (name "unconnected-(U4-NC-Pad9)") (class "Default")
      (node (ref "U4") (pin "9") (pinfunction "NC_9") (pintype "passive+no_connect"))
    )
  )
)
